# visp-i2c-mux-bmp388.net
KiCad netlist of a schematic drawn in EAGLE
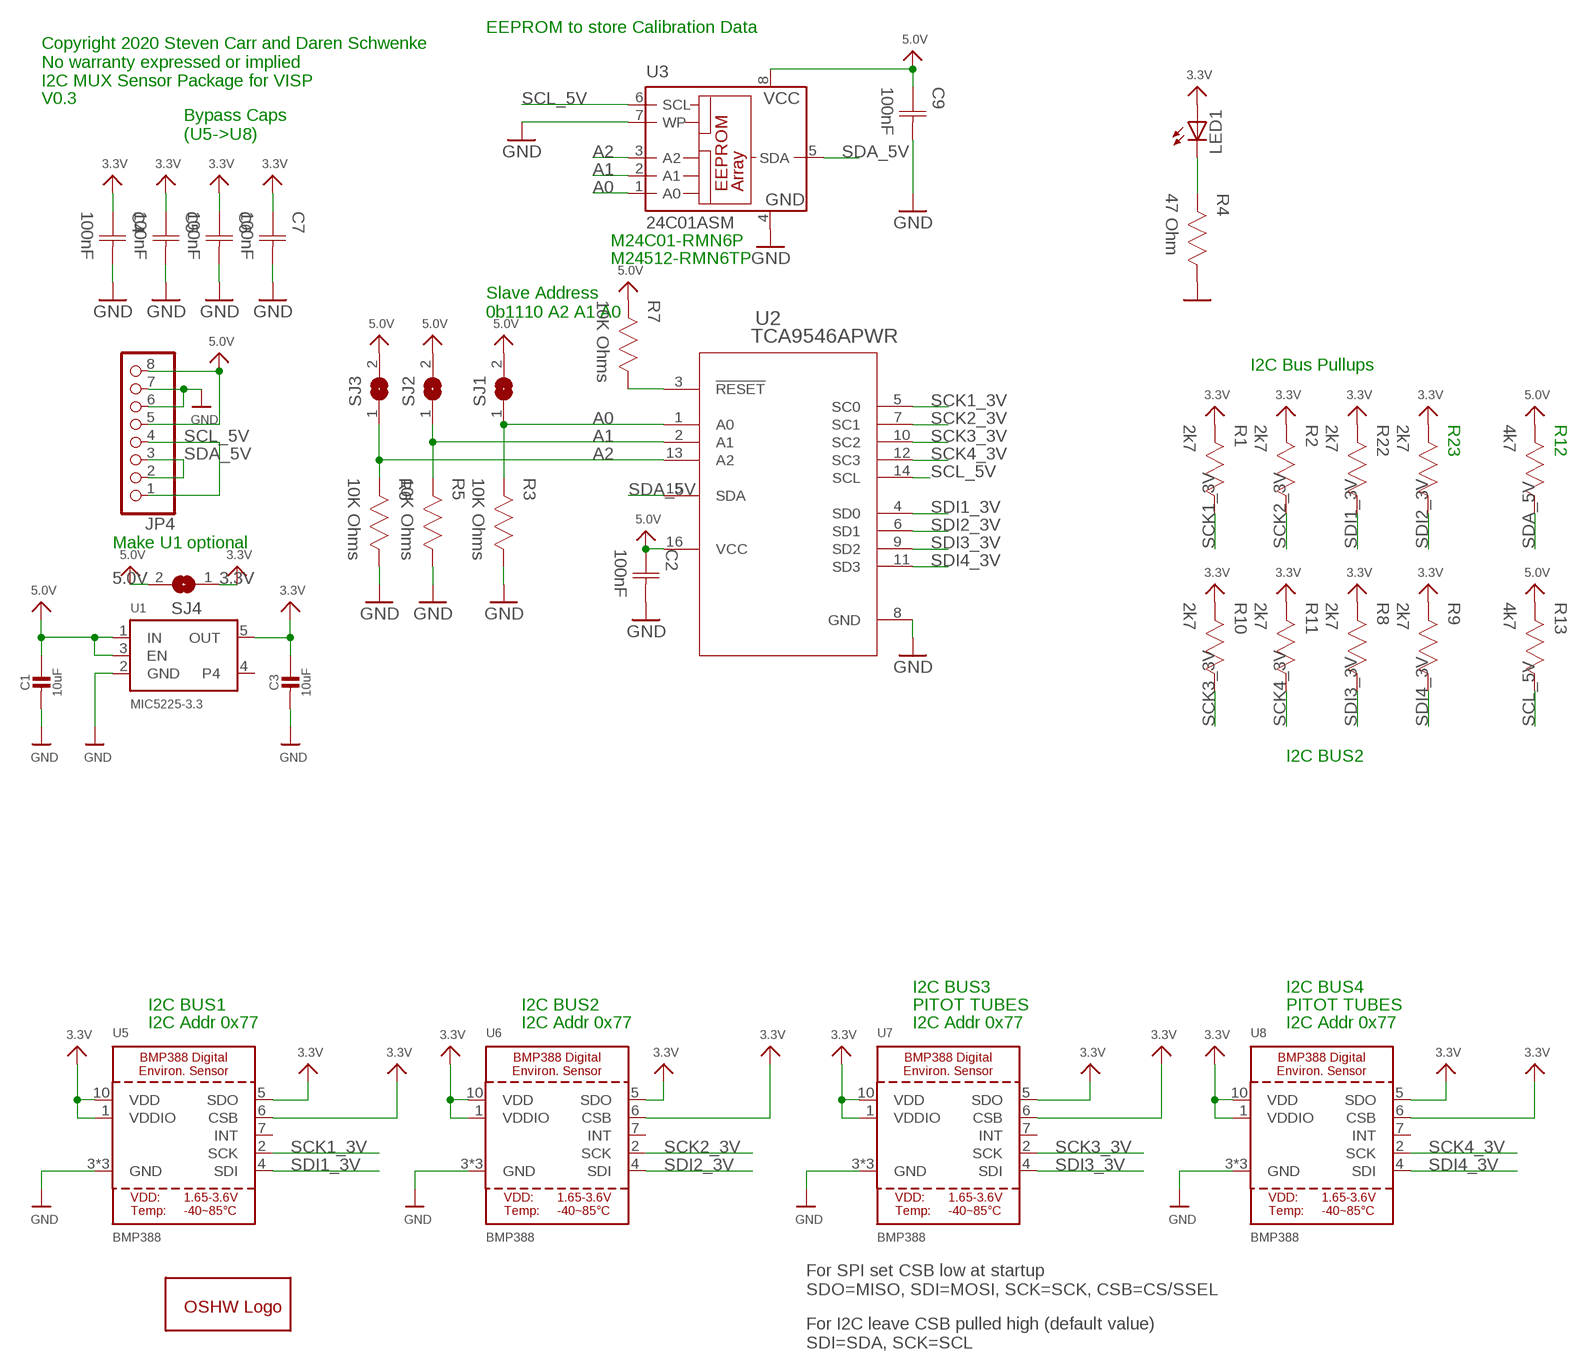
[diagram p0: schematic, sheet 1]

(export (version "E")
  (design (tool "Eeschema 10.0.6"))
  (components
    (comp (ref "C1")
      (value "10uF")
      (footprint "eagle-import:_0805")
      (fields (field (name "MPN") "C1608X5R1A106M080AC"))
      (libsource (lib "eagle-import") (part "CAP_CERAMIC_0805"))
    )
    (comp (ref "C2")
      (value "100nF")
      (footprint "eagle-import:CAP0402")
      (fields (field (name "MPN") "CL10B104KB8NNNC"))
      (libsource (lib "eagle-import") (part "CAPACITOR-0402"))
    )
    (comp (ref "C3")
      (value "10uF")
      (footprint "eagle-import:_0805")
      (fields (field (name "MPN") "C1608X5R1A106M080AC"))
      (libsource (lib "eagle-import") (part "CAP_CERAMIC_0805"))
    )
    (comp (ref "C4")
      (value "100nF")
      (footprint "eagle-import:CAP0402")
      (fields (field (name "MPN") " CL10F104ZO8NNNC "))
      (libsource (lib "eagle-import") (part "CAPACITOR-0402"))
    )
    (comp (ref "C5")
      (value "100nF")
      (footprint "eagle-import:CAP0402")
      (fields (field (name "MPN") " CL10F104ZO8NNNC "))
      (libsource (lib "eagle-import") (part "CAPACITOR-0402"))
    )
    (comp (ref "C6")
      (value "100nF")
      (footprint "eagle-import:CAP0402")
      (fields (field (name "MPN") " CL10F104ZO8NNNC "))
      (libsource (lib "eagle-import") (part "CAPACITOR-0402"))
    )
    (comp (ref "C7")
      (value "100nF")
      (footprint "eagle-import:CAP0402")
      (fields (field (name "MPN") " CL10F104ZO8NNNC "))
      (libsource (lib "eagle-import") (part "CAPACITOR-0402"))
    )
    (comp (ref "C9")
      (value "100nF")
      (footprint "eagle-import:CAP0402")
      (fields (field (name "MPN") "CL10B104KB8NNNC"))
      (libsource (lib "eagle-import") (part "CAPACITOR-0402"))
    )
    (comp (ref "GOLD_ORB_SM1")
      (value "OSHWLOGOLOGO8MM")
      (footprint "eagle-import:OSHW_8MM")
      (libsource (lib "eagle-import") (part "OSHWLOGOLOGO8MM"))
    )
    (comp (ref "JP4")
      (value "PINHD-1X08_2.54")
      (footprint "eagle-import:1X08")
      (libsource (lib "eagle-import") (part "PINHD-1X08_2.54"))
    )
    (comp (ref "LED1")
      (value "LEDCHIP-LED0603")
      (footprint "eagle-import:CHIP-LED0603")
      (fields (field (name "MPN") "SML-D12P8WT86"))
      (libsource (lib "eagle-import") (part "LEDCHIP-LED0603"))
    )
    (comp (ref "R1")
      (value "2k7")
      (footprint "eagle-import:RES0402")
      (fields (field (name "MPN") "CRCW060310K0FKEAC"))
      (libsource (lib "eagle-import") (part "RESISTOR-0402"))
    )
    (comp (ref "R2")
      (value "2k7")
      (footprint "eagle-import:RES0402")
      (fields (field (name "MPN") "CRCW060310K0FKEAC"))
      (libsource (lib "eagle-import") (part "RESISTOR-0402"))
    )
    (comp (ref "R3")
      (value "10K Ohms")
      (footprint "eagle-import:RES0402")
      (fields (field (name "MPN") "CRCW060310K0FKEAC"))
      (libsource (lib "eagle-import") (part "RESISTOR-0402"))
    )
    (comp (ref "R4")
      (value "47 Ohm")
      (footprint "eagle-import:RES0402")
      (fields (field (name "MPN") "RC0603FR-0747RL"))
      (libsource (lib "eagle-import") (part "RESISTOR-0402"))
    )
    (comp (ref "R5")
      (value "10K Ohms")
      (footprint "eagle-import:RES0402")
      (fields (field (name "MPN") "CRCW060310K0FKEAC"))
      (libsource (lib "eagle-import") (part "RESISTOR-0402"))
    )
    (comp (ref "R6")
      (value "10K Ohms")
      (footprint "eagle-import:RES0402")
      (fields (field (name "MPN") "CRCW060310K0FKEAC"))
      (libsource (lib "eagle-import") (part "RESISTOR-0402"))
    )
    (comp (ref "R7")
      (value "10K Ohms")
      (footprint "eagle-import:RES0402")
      (fields (field (name "MPN") "CRCW060310K0FKEAC"))
      (libsource (lib "eagle-import") (part "RESISTOR-0402"))
    )
    (comp (ref "R8")
      (value "2k7")
      (footprint "eagle-import:RES0402")
      (fields (field (name "MPN") "CRCW060310K0FKEAC"))
      (libsource (lib "eagle-import") (part "RESISTOR-0402"))
    )
    (comp (ref "R9")
      (value "2k7")
      (footprint "eagle-import:RES0402")
      (fields (field (name "MPN") "CRCW060310K0FKEAC"))
      (libsource (lib "eagle-import") (part "RESISTOR-0402"))
    )
    (comp (ref "R10")
      (value "2k7")
      (footprint "eagle-import:RES0402")
      (fields (field (name "MPN") "CRCW060310K0FKEAC"))
      (libsource (lib "eagle-import") (part "RESISTOR-0402"))
    )
    (comp (ref "R11")
      (value "2k7")
      (footprint "eagle-import:RES0402")
      (fields (field (name "MPN") "CRCW060310K0FKEAC"))
      (libsource (lib "eagle-import") (part "RESISTOR-0402"))
    )
    (comp (ref "R12")
      (value "4k7")
      (footprint "eagle-import:RES0402")
      (fields (field (name "MPN") "CRCW060310K0FKEAC"))
      (libsource (lib "eagle-import") (part "RESISTOR-0402"))
    )
    (comp (ref "R13")
      (value "4k7")
      (footprint "eagle-import:RES0402")
      (fields (field (name "MPN") "CRCW060310K0FKEAC"))
      (libsource (lib "eagle-import") (part "RESISTOR-0402"))
    )
    (comp (ref "R22")
      (value "2k7")
      (footprint "eagle-import:RES0402")
      (fields (field (name "MPN") "CRCW060310K0FKEAC"))
      (libsource (lib "eagle-import") (part "RESISTOR-0402"))
    )
    (comp (ref "R23")
      (value "2k7")
      (footprint "eagle-import:RES0402")
      (fields (field (name "MPN") "CRCW060310K0FKEAC"))
      (libsource (lib "eagle-import") (part "RESISTOR-0402"))
    )
    (comp (ref "SJ1") (value "SJ") (footprint "eagle-import:SJ") (libsource (lib "eagle-import") (part "SJ")))
    (comp (ref "SJ2") (value "SJ") (footprint "eagle-import:SJ") (libsource (lib "eagle-import") (part "SJ")))
    (comp (ref "SJ3") (value "SJ") (footprint "eagle-import:SJ") (libsource (lib "eagle-import") (part "SJ")))
    (comp (ref "SJ4") (value "SJ") (footprint "eagle-import:SJ") (libsource (lib "eagle-import") (part "SJ")))
    (comp (ref "U1")
      (value "MIC5225-3.3")
      (footprint "eagle-import:SOT23-5")
      (fields (field (name "MPN") "MIC5225-3.3YM5-TR"))
      (libsource (lib "eagle-import") (part "VREG_SOT23-5"))
    )
    (comp (ref "U2")
      (value "TCA9546APWR")
      (footprint "eagle-import:PW16")
      (libsource (lib "eagle-import") (part "TCA9546APWR"))
    )
    (comp (ref "U3")
      (value "24C01ASM")
      (footprint "eagle-import:SO-08M")
      (fields
        (field (name "MF") "MICROCHIP")
        (field (name "MPN") "24C01C/SN")
        (field (name "MPN_1") "M24C01-RMN6P")
      )
      (libsource (lib "eagle-import") (part "24SMC01A"))
    )
    (comp (ref "U5")
      (value "BMP388")
      (footprint "eagle-import:BMP388")
      (libsource (lib "eagle-import") (part "BMP388"))
    )
    (comp (ref "U6")
      (value "BMP388")
      (footprint "eagle-import:BMP388")
      (libsource (lib "eagle-import") (part "BMP388"))
    )
    (comp (ref "U7")
      (value "BMP388")
      (footprint "eagle-import:BMP388")
      (libsource (lib "eagle-import") (part "BMP388"))
    )
    (comp (ref "U8")
      (value "BMP388")
      (footprint "eagle-import:BMP388")
      (libsource (lib "eagle-import") (part "BMP388"))
    )
  )
  (nets
    (net (code "1") (name "/A0") (class "Default")
      (node (ref "R3") (pin "2") (pinfunction "2_2") (pintype "passive"))
      (node (ref "SJ1") (pin "1") (pinfunction "1_1") (pintype "passive"))
      (node (ref "U2") (pin "1") (pinfunction "A0_1") (pintype "input"))
      (node (ref "U3") (pin "1") (pinfunction "A0_1") (pintype "input"))
    )
    (net (code "2") (name "/A1") (class "Default")
      (node (ref "R5") (pin "2") (pinfunction "2_2") (pintype "passive"))
      (node (ref "SJ2") (pin "1") (pinfunction "1_1") (pintype "passive"))
      (node (ref "U2") (pin "2") (pinfunction "A1_2") (pintype "input"))
      (node (ref "U3") (pin "2") (pinfunction "A1_2") (pintype "input"))
    )
    (net (code "3") (name "/A2") (class "Default")
      (node (ref "R6") (pin "2") (pinfunction "2_2") (pintype "passive"))
      (node (ref "SJ3") (pin "1") (pinfunction "1_1") (pintype "passive"))
      (node (ref "U2") (pin "13") (pinfunction "A2_13") (pintype "input"))
      (node (ref "U3") (pin "3") (pinfunction "A2_3") (pintype "input"))
    )
    (net (code "4") (name "/SCK1_3V") (class "Default")
      (node (ref "R1") (pin "1") (pinfunction "1_1") (pintype "passive"))
      (node (ref "U2") (pin "5") (pinfunction "SC0_5") (pintype "passive"))
      (node (ref "U5") (pin "2") (pinfunction "SCK_2") (pintype "input"))
    )
    (net (code "5") (name "/SCK2_3V") (class "Default")
      (node (ref "R2") (pin "1") (pinfunction "1_1") (pintype "passive"))
      (node (ref "U2") (pin "7") (pinfunction "SC1_7") (pintype "passive"))
      (node (ref "U6") (pin "2") (pinfunction "SCK_2") (pintype "input"))
    )
    (net (code "6") (name "/SCK3_3V") (class "Default")
      (node (ref "R10") (pin "1") (pinfunction "1_1") (pintype "passive"))
      (node (ref "U2") (pin "10") (pinfunction "SC2_10") (pintype "passive"))
      (node (ref "U7") (pin "2") (pinfunction "SCK_2") (pintype "input"))
    )
    (net (code "7") (name "/SCK4_3V") (class "Default")
      (node (ref "R11") (pin "1") (pinfunction "1_1") (pintype "passive"))
      (node (ref "U2") (pin "12") (pinfunction "SC3_12") (pintype "passive"))
      (node (ref "U8") (pin "2") (pinfunction "SCK_2") (pintype "input"))
    )
    (net (code "8") (name "/SCL_5V") (class "Default")
      (node (ref "JP4") (pin "1") (pinfunction "1_1") (pintype "passive"))
      (node (ref "JP4") (pin "4") (pinfunction "4_4") (pintype "passive"))
      (node (ref "R13") (pin "1") (pinfunction "1_1") (pintype "passive"))
      (node (ref "U2") (pin "14") (pinfunction "SCL_14") (pintype "passive"))
      (node (ref "U3") (pin "6") (pinfunction "SCL_6") (pintype "input"))
    )
    (net (code "9") (name "/SDA_5V") (class "Default")
      (node (ref "JP4") (pin "2") (pinfunction "2_2") (pintype "passive"))
      (node (ref "JP4") (pin "3") (pinfunction "3_3") (pintype "passive"))
      (node (ref "R12") (pin "1") (pinfunction "1_1") (pintype "passive"))
      (node (ref "U2") (pin "15") (pinfunction "SDA_15") (pintype "passive"))
      (node (ref "U3") (pin "5") (pinfunction "SDA_5") (pintype "bidirectional"))
    )
    (net (code "10") (name "/SDI1_3V") (class "Default")
      (node (ref "R22") (pin "1") (pinfunction "1_1") (pintype "passive"))
      (node (ref "U2") (pin "4") (pinfunction "SD0_4") (pintype "passive"))
      (node (ref "U5") (pin "4") (pinfunction "SDI_4") (pintype "input"))
    )
    (net (code "11") (name "/SDI2_3V") (class "Default")
      (node (ref "R23") (pin "1") (pinfunction "1_1") (pintype "passive"))
      (node (ref "U2") (pin "6") (pinfunction "SD1_6") (pintype "passive"))
      (node (ref "U6") (pin "4") (pinfunction "SDI_4") (pintype "input"))
    )
    (net (code "12") (name "/SDI3_3V") (class "Default")
      (node (ref "R8") (pin "1") (pinfunction "1_1") (pintype "passive"))
      (node (ref "U2") (pin "9") (pinfunction "SD2_9") (pintype "passive"))
      (node (ref "U7") (pin "4") (pinfunction "SDI_4") (pintype "input"))
    )
    (net (code "13") (name "/SDI4_3V") (class "Default")
      (node (ref "R9") (pin "1") (pinfunction "1_1") (pintype "passive"))
      (node (ref "U2") (pin "11") (pinfunction "SD3_11") (pintype "passive"))
      (node (ref "U8") (pin "4") (pinfunction "SDI_4") (pintype "input"))
    )
    (net (code "14") (name "3.3V") (class "Default")
      (node (ref "C3") (pin "1") (pinfunction "1_1") (pintype "passive"))
      (node (ref "C4") (pin "1") (pinfunction "C1_1") (pintype "passive"))
      (node (ref "C5") (pin "1") (pinfunction "C1_1") (pintype "passive"))
      (node (ref "C6") (pin "1") (pinfunction "C1_1") (pintype "passive"))
      (node (ref "C7") (pin "1") (pinfunction "C1_1") (pintype "passive"))
      (node (ref "LED1") (pin "A") (pinfunction "A_A") (pintype "passive"))
      (node (ref "R1") (pin "2") (pinfunction "2_2") (pintype "passive"))
      (node (ref "R10") (pin "2") (pinfunction "2_2") (pintype "passive"))
      (node (ref "R11") (pin "2") (pinfunction "2_2") (pintype "passive"))
      (node (ref "R2") (pin "2") (pinfunction "2_2") (pintype "passive"))
      (node (ref "R22") (pin "2") (pinfunction "2_2") (pintype "passive"))
      (node (ref "R23") (pin "2") (pinfunction "2_2") (pintype "passive"))
      (node (ref "R8") (pin "2") (pinfunction "2_2") (pintype "passive"))
      (node (ref "R9") (pin "2") (pinfunction "2_2") (pintype "passive"))
      (node (ref "SJ4") (pin "1") (pinfunction "1_1") (pintype "passive"))
      (node (ref "U1") (pin "5") (pinfunction "OUT_5") (pintype "power_in"))
      (node (ref "U5") (pin "1") (pinfunction "VDDIO_1") (pintype "power_in"))
      (node (ref "U5") (pin "10") (pinfunction "VDD_10") (pintype "power_in"))
      (node (ref "U5") (pin "5") (pinfunction "SDO_5") (pintype "output"))
      (node (ref "U5") (pin "6") (pinfunction "CSB_6") (pintype "input"))
      (node (ref "U6") (pin "1") (pinfunction "VDDIO_1") (pintype "power_in"))
      (node (ref "U6") (pin "10") (pinfunction "VDD_10") (pintype "power_in"))
      (node (ref "U6") (pin "5") (pinfunction "SDO_5") (pintype "output"))
      (node (ref "U6") (pin "6") (pinfunction "CSB_6") (pintype "input"))
      (node (ref "U7") (pin "1") (pinfunction "VDDIO_1") (pintype "power_in"))
      (node (ref "U7") (pin "10") (pinfunction "VDD_10") (pintype "power_in"))
      (node (ref "U7") (pin "5") (pinfunction "SDO_5") (pintype "output"))
      (node (ref "U7") (pin "6") (pinfunction "CSB_6") (pintype "input"))
      (node (ref "U8") (pin "1") (pinfunction "VDDIO_1") (pintype "power_in"))
      (node (ref "U8") (pin "10") (pinfunction "VDD_10") (pintype "power_in"))
      (node (ref "U8") (pin "5") (pinfunction "SDO_5") (pintype "output"))
      (node (ref "U8") (pin "6") (pinfunction "CSB_6") (pintype "input"))
    )
    (net (code "15") (name "5.0V") (class "Default")
      (node (ref "C1") (pin "1") (pinfunction "1_1") (pintype "passive"))
      (node (ref "C2") (pin "1") (pinfunction "C1_1") (pintype "passive"))
      (node (ref "C9") (pin "1") (pinfunction "C1_1") (pintype "passive"))
      (node (ref "JP4") (pin "5") (pinfunction "5_5") (pintype "passive"))
      (node (ref "JP4") (pin "8") (pinfunction "8_8") (pintype "passive"))
      (node (ref "R12") (pin "2") (pinfunction "2_2") (pintype "passive"))
      (node (ref "R13") (pin "2") (pinfunction "2_2") (pintype "passive"))
      (node (ref "R7") (pin "2") (pinfunction "2_2") (pintype "passive"))
      (node (ref "SJ1") (pin "2") (pinfunction "2_2") (pintype "passive"))
      (node (ref "SJ2") (pin "2") (pinfunction "2_2") (pintype "passive"))
      (node (ref "SJ3") (pin "2") (pinfunction "2_2") (pintype "passive"))
      (node (ref "SJ4") (pin "2") (pinfunction "2_2") (pintype "passive"))
      (node (ref "U1") (pin "1") (pinfunction "IN_1") (pintype "power_in"))
      (node (ref "U1") (pin "3") (pinfunction "EN_3") (pintype "input"))
      (node (ref "U2") (pin "16") (pinfunction "VCC_16") (pintype "power_in"))
      (node (ref "U3") (pin "8") (pinfunction "VCC_8") (pintype "power_in"))
    )
    (net (code "16") (name "GND") (class "Default")
      (node (ref "C1") (pin "2") (pinfunction "2_2") (pintype "passive"))
      (node (ref "C2") (pin "2") (pinfunction "C2_2") (pintype "passive"))
      (node (ref "C3") (pin "2") (pinfunction "2_2") (pintype "passive"))
      (node (ref "C4") (pin "2") (pinfunction "C2_2") (pintype "passive"))
      (node (ref "C5") (pin "2") (pinfunction "C2_2") (pintype "passive"))
      (node (ref "C6") (pin "2") (pinfunction "C2_2") (pintype "passive"))
      (node (ref "C7") (pin "2") (pinfunction "C2_2") (pintype "passive"))
      (node (ref "C9") (pin "2") (pinfunction "C2_2") (pintype "passive"))
      (node (ref "JP4") (pin "6") (pinfunction "6_6") (pintype "passive"))
      (node (ref "JP4") (pin "7") (pinfunction "7_7") (pintype "passive"))
      (node (ref "R3") (pin "1") (pinfunction "1_1") (pintype "passive"))
      (node (ref "R4") (pin "1") (pinfunction "1_1") (pintype "passive"))
      (node (ref "R5") (pin "1") (pinfunction "1_1") (pintype "passive"))
      (node (ref "R6") (pin "1") (pinfunction "1_1") (pintype "passive"))
      (node (ref "U1") (pin "2") (pinfunction "GND_2") (pintype "power_in"))
      (node (ref "U2") (pin "8") (pinfunction "GND_8") (pintype "power_in"))
      (node (ref "U3") (pin "4") (pinfunction "GND_4") (pintype "power_in"))
      (node (ref "U3") (pin "7") (pinfunction "WP_7") (pintype "input"))
      (node (ref "U5") (pin "3") (pinfunction "GND_3") (pintype "power_in"))
      (node (ref "U5") (pin "8") (pinfunction "GND_8") (pintype "power_in"))
      (node (ref "U5") (pin "9") (pinfunction "GND_9") (pintype "power_in"))
      (node (ref "U6") (pin "3") (pinfunction "GND_3") (pintype "power_in"))
      (node (ref "U6") (pin "8") (pinfunction "GND_8") (pintype "power_in"))
      (node (ref "U6") (pin "9") (pinfunction "GND_9") (pintype "power_in"))
      (node (ref "U7") (pin "3") (pinfunction "GND_3") (pintype "power_in"))
      (node (ref "U7") (pin "8") (pinfunction "GND_8") (pintype "power_in"))
      (node (ref "U7") (pin "9") (pinfunction "GND_9") (pintype "power_in"))
      (node (ref "U8") (pin "3") (pinfunction "GND_3") (pintype "power_in"))
      (node (ref "U8") (pin "8") (pinfunction "GND_8") (pintype "power_in"))
      (node (ref "U8") (pin "9") (pinfunction "GND_9") (pintype "power_in"))
    )
    (net (code "17") (name "Net-(LED1-PadC)") (class "Default")
      (node (ref "LED1") (pin "C") (pinfunction "C_C") (pintype "passive"))
      (node (ref "R4") (pin "2") (pinfunction "2_2") (pintype "passive"))
    )
    (net (code "18") (name "Net-(U2-~{RESET})") (class "Default")
      (node (ref "R7") (pin "1") (pinfunction "1_1") (pintype "passive"))
      (node (ref "U2") (pin "3") (pinfunction "~{RESET}_3") (pintype "input"))
    )
    (net (code "19") (name "unconnected-(U1-P4-Pad4)") (class "Default")
      (node (ref "U1") (pin "4") (pinfunction "P4_4") (pintype "bidirectional"))
    )
    (net (code "20") (name "unconnected-(U5-INT-Pad7)") (class "Default")
      (node (ref "U5") (pin "7") (pinfunction "INT_7") (pintype "output"))
    )
    (net (code "21") (name "unconnected-(U6-INT-Pad7)") (class "Default")
      (node (ref "U6") (pin "7") (pinfunction "INT_7") (pintype "output"))
    )
    (net (code "22") (name "unconnected-(U7-INT-Pad7)") (class "Default")
      (node (ref "U7") (pin "7") (pinfunction "INT_7") (pintype "output"))
    )
    (net (code "23") (name "unconnected-(U8-INT-Pad7)") (class "Default")
      (node (ref "U8") (pin "7") (pinfunction "INT_7") (pintype "output"))
    )
  )
)
